# Watch.net
KiCad netlist of a schematic drawn in Altium Designer
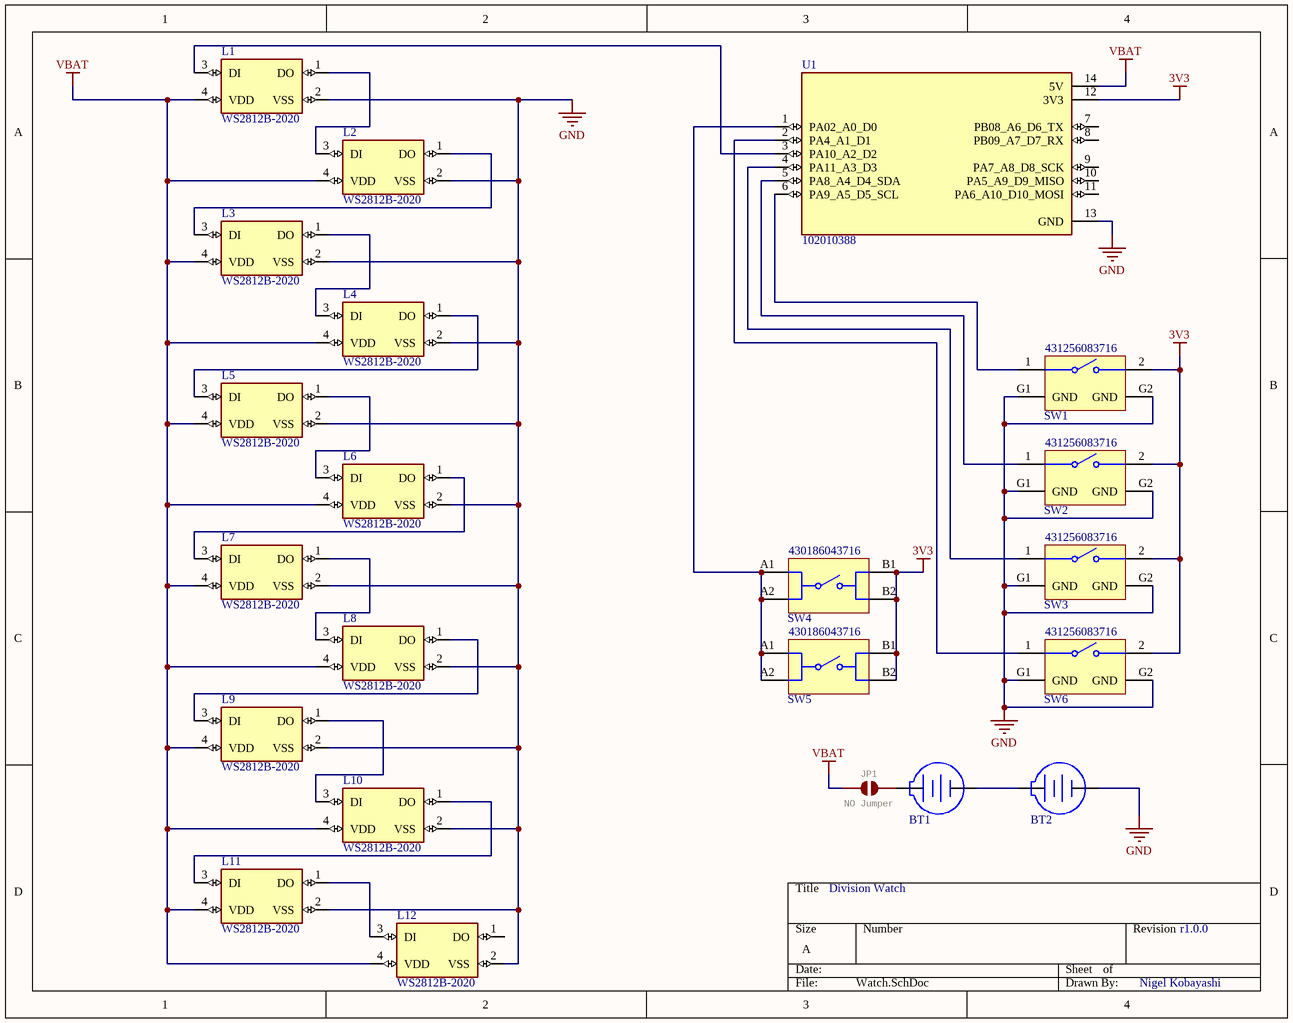
[diagram p0: Watch.SchDoc]

(export (version "E")
  (design (tool "Eeschema 10.0.6"))
  (components
    (comp (ref "BT1")
      (value "79523141")
      (footprint "79523141")
      (description "WA-BCMC Battery Holder, SMT, battery type 2016,2020,2025,2032")
      (fields (field (name "MANUFACTURER") "Wurth Elektronik"))
      (libsource (lib "WE - Electromechanical Components") (part "Battery Holder"))
    )
    (comp (ref "BT2")
      (value "79523141")
      (footprint "79523141")
      (description "WA-BCMC Battery Holder, SMT, battery type 2016,2020,2025,2032")
      (fields (field (name "MANUFACTURER") "Wurth Elektronik"))
      (libsource (lib "WE - Electromechanical Components") (part "Battery Holder"))
    )
    (comp (ref "JP1")
      (value "NO Jumper")
      (footprint "SMT-JUMPER_2_NO_SILK")
      (libsource (lib "SparkFun-Jumpers.Library") (part "JUMPER-SMT_2_NO_SILK"))
    )
    (comp (ref "L1")
      (value "WS2812B-2020")
      (footprint "WS2812B-2020")
      (description "Programmable LED; SMD; 2020; RGB; 2x2x0.84mm; 3.7Ã·5.3V; 2kHz")
      (fields (field (name "MF") "WorldSemi"))
      (libsource (lib "WS2812B-2020") (part "WS2812B-2020"))
    )
    (comp (ref "L2")
      (value "WS2812B-2020")
      (footprint "WS2812B-2020")
      (description "Programmable LED; SMD; 2020; RGB; 2x2x0.84mm; 3.7Ã·5.3V; 2kHz")
      (fields (field (name "MF") "WorldSemi"))
      (libsource (lib "WS2812B-2020") (part "WS2812B-2020"))
    )
    (comp (ref "L3")
      (value "WS2812B-2020")
      (footprint "WS2812B-2020")
      (description "Programmable LED; SMD; 2020; RGB; 2x2x0.84mm; 3.7Ã·5.3V; 2kHz")
      (fields (field (name "MF") "WorldSemi"))
      (libsource (lib "WS2812B-2020") (part "WS2812B-2020"))
    )
    (comp (ref "L4")
      (value "WS2812B-2020")
      (footprint "WS2812B-2020")
      (description "Programmable LED; SMD; 2020; RGB; 2x2x0.84mm; 3.7Ã·5.3V; 2kHz")
      (fields (field (name "MF") "WorldSemi"))
      (libsource (lib "WS2812B-2020") (part "WS2812B-2020"))
    )
    (comp (ref "L5")
      (value "WS2812B-2020")
      (footprint "WS2812B-2020")
      (description "Programmable LED; SMD; 2020; RGB; 2x2x0.84mm; 3.7Ã·5.3V; 2kHz")
      (fields (field (name "MF") "WorldSemi"))
      (libsource (lib "WS2812B-2020") (part "WS2812B-2020"))
    )
    (comp (ref "L6")
      (value "WS2812B-2020")
      (footprint "WS2812B-2020")
      (description "Programmable LED; SMD; 2020; RGB; 2x2x0.84mm; 3.7Ã·5.3V; 2kHz")
      (fields (field (name "MF") "WorldSemi"))
      (libsource (lib "WS2812B-2020") (part "WS2812B-2020"))
    )
    (comp (ref "L7")
      (value "WS2812B-2020")
      (footprint "WS2812B-2020")
      (description "Programmable LED; SMD; 2020; RGB; 2x2x0.84mm; 3.7Ã·5.3V; 2kHz")
      (fields (field (name "MF") "WorldSemi"))
      (libsource (lib "WS2812B-2020") (part "WS2812B-2020"))
    )
    (comp (ref "L8")
      (value "WS2812B-2020")
      (footprint "WS2812B-2020")
      (description "Programmable LED; SMD; 2020; RGB; 2x2x0.84mm; 3.7Ã·5.3V; 2kHz")
      (fields (field (name "MF") "WorldSemi"))
      (libsource (lib "WS2812B-2020") (part "WS2812B-2020"))
    )
    (comp (ref "L9")
      (value "WS2812B-2020")
      (footprint "WS2812B-2020")
      (description "Programmable LED; SMD; 2020; RGB; 2x2x0.84mm; 3.7Ã·5.3V; 2kHz")
      (fields (field (name "MF") "WorldSemi"))
      (libsource (lib "WS2812B-2020") (part "WS2812B-2020"))
    )
    (comp (ref "L10")
      (value "WS2812B-2020")
      (footprint "WS2812B-2020")
      (description "Programmable LED; SMD; 2020; RGB; 2x2x0.84mm; 3.7Ã·5.3V; 2kHz")
      (fields (field (name "MF") "WorldSemi"))
      (libsource (lib "WS2812B-2020") (part "WS2812B-2020"))
    )
    (comp (ref "L11")
      (value "WS2812B-2020")
      (footprint "WS2812B-2020")
      (description "Programmable LED; SMD; 2020; RGB; 2x2x0.84mm; 3.7Ã·5.3V; 2kHz")
      (fields (field (name "MF") "WorldSemi"))
      (libsource (lib "WS2812B-2020") (part "WS2812B-2020"))
    )
    (comp (ref "L12")
      (value "WS2812B-2020")
      (footprint "WS2812B-2020")
      (description "Programmable LED; SMD; 2020; RGB; 2x2x0.84mm; 3.7Ã·5.3V; 2kHz")
      (fields (field (name "MF") "WorldSemi"))
      (libsource (lib "WS2812B-2020") (part "WS2812B-2020"))
    )
    (comp (ref "SW1")
      (value "431256083716")
      (footprint "4312560837x6")
      (description "WS-TATU THT Tact Switch 6x6mm Right Angled Type with ground terminal, SPST-NO, 12VDC, 50mA, 160g")
      (fields (field (name "MANUFACTURER") "Wurth Elektronik"))
      (libsource (lib "WE - Electromechanical Components") (part "SPST-NO_2P_2GND"))
    )
    (comp (ref "SW2")
      (value "431256083716")
      (footprint "4312560837x6")
      (description "WS-TATU THT Tact Switch 6x6mm Right Angled Type with ground terminal, SPST-NO, 12VDC, 50mA, 160g")
      (fields (field (name "MANUFACTURER") "Wurth Elektronik"))
      (libsource (lib "WE - Electromechanical Components") (part "SPST-NO_2P_2GND"))
    )
    (comp (ref "SW3")
      (value "431256083716")
      (footprint "4312560837x6")
      (description "WS-TATU THT Tact Switch 6x6mm Right Angled Type with ground terminal, SPST-NO, 12VDC, 50mA, 160g")
      (fields (field (name "MANUFACTURER") "Wurth Elektronik"))
      (libsource (lib "WE - Electromechanical Components") (part "SPST-NO_2P_2GND"))
    )
    (comp (ref "SW4")
      (value "430186043716")
      (footprint "4301x60437x6")
      (description "WS-TATV THT Tact Switch 6x6mm, SPST-NO, 12VDC, 50mA, 160g")
      (fields (field (name "MANUFACTURER") "Wurth Elektronik"))
      (libsource (lib "WE - Electromechanical Components") (part "SPST-NO_4P"))
    )
    (comp (ref "SW5")
      (value "430186043716")
      (footprint "4301x60437x6")
      (description "WS-TATV THT Tact Switch 6x6mm, SPST-NO, 12VDC, 50mA, 160g")
      (fields (field (name "MANUFACTURER") "Wurth Elektronik"))
      (libsource (lib "WE - Electromechanical Components") (part "SPST-NO_4P"))
    )
    (comp (ref "SW6")
      (value "431256083716")
      (footprint "4312560837x6")
      (description "WS-TATU THT Tact Switch 6x6mm Right Angled Type with ground terminal, SPST-NO, 12VDC, 50mA, 160g")
      (fields (field (name "MANUFACTURER") "Wurth Elektronik"))
      (libsource (lib "WE - Electromechanical Components") (part "SPST-NO_2P_2GND"))
    )
    (comp (ref "U1")
      (value "102010388")
      (footprint "MODULE_102010388")
      (fields (field (name "MF") "Seeed Technology Co., Ltd"))
      (libsource (lib "102010388") (part "102010388"))
    )
  )
  (nets
    (net (code "1") (name "3V3") (class "Default")
      (node (ref "SW1") (pin "2") (pinfunction "2_2") (pintype "passive"))
      (node (ref "SW2") (pin "2") (pinfunction "2_2") (pintype "passive"))
      (node (ref "SW3") (pin "2") (pinfunction "2_2") (pintype "passive"))
      (node (ref "SW4") (pin "B1") (pinfunction "B1_B1") (pintype "passive"))
      (node (ref "SW4") (pin "B2") (pinfunction "B2_B2") (pintype "passive"))
      (node (ref "SW5") (pin "B1") (pinfunction "B1_B1") (pintype "passive"))
      (node (ref "SW5") (pin "B2") (pinfunction "B2_B2") (pintype "passive"))
      (node (ref "SW6") (pin "2") (pinfunction "2_2") (pintype "passive"))
      (node (ref "U1") (pin "12") (pinfunction "3V3_12") (pintype "power_in"))
    )
    (net (code "2") (name "GND") (class "Default")
      (node (ref "BT2") (pin "2") (pinfunction "-_2") (pintype "passive"))
      (node (ref "L1") (pin "2") (pinfunction "VSS_2") (pintype "bidirectional"))
      (node (ref "L10") (pin "2") (pinfunction "VSS_2") (pintype "bidirectional"))
      (node (ref "L11") (pin "2") (pinfunction "VSS_2") (pintype "bidirectional"))
      (node (ref "L12") (pin "2") (pinfunction "VSS_2") (pintype "bidirectional"))
      (node (ref "L2") (pin "2") (pinfunction "VSS_2") (pintype "bidirectional"))
      (node (ref "L3") (pin "2") (pinfunction "VSS_2") (pintype "bidirectional"))
      (node (ref "L4") (pin "2") (pinfunction "VSS_2") (pintype "bidirectional"))
      (node (ref "L5") (pin "2") (pinfunction "VSS_2") (pintype "bidirectional"))
      (node (ref "L6") (pin "2") (pinfunction "VSS_2") (pintype "bidirectional"))
      (node (ref "L7") (pin "2") (pinfunction "VSS_2") (pintype "bidirectional"))
      (node (ref "L8") (pin "2") (pinfunction "VSS_2") (pintype "bidirectional"))
      (node (ref "L9") (pin "2") (pinfunction "VSS_2") (pintype "bidirectional"))
      (node (ref "SW1") (pin "G1") (pinfunction "GND_G1") (pintype "passive"))
      (node (ref "SW1") (pin "G2") (pinfunction "GND_G2") (pintype "passive"))
      (node (ref "SW2") (pin "G1") (pinfunction "GND_G1") (pintype "passive"))
      (node (ref "SW2") (pin "G2") (pinfunction "GND_G2") (pintype "passive"))
      (node (ref "SW3") (pin "G1") (pinfunction "GND_G1") (pintype "passive"))
      (node (ref "SW3") (pin "G2") (pinfunction "GND_G2") (pintype "passive"))
      (node (ref "SW6") (pin "G1") (pinfunction "GND_G1") (pintype "passive"))
      (node (ref "SW6") (pin "G2") (pinfunction "GND_G2") (pintype "passive"))
      (node (ref "U1") (pin "13") (pinfunction "GND_13") (pintype "power_in"))
    )
    (net (code "3") (name "Net-(BT1-+)") (class "Default")
      (node (ref "BT1") (pin "1") (pinfunction "+_1") (pintype "passive"))
      (node (ref "JP1") (pin "2") (pinfunction "2_2") (pintype "passive"))
    )
    (net (code "4") (name "Net-(BT1--)") (class "Default")
      (node (ref "BT1") (pin "2") (pinfunction "-_2") (pintype "passive"))
      (node (ref "BT2") (pin "1") (pinfunction "+_1") (pintype "passive"))
    )
    (net (code "5") (name "Net-(L1-DI)") (class "Default")
      (node (ref "L1") (pin "3") (pinfunction "DI_3") (pintype "bidirectional"))
      (node (ref "U1") (pin "3") (pinfunction "PA10_A2_D2_3") (pintype "bidirectional"))
    )
    (net (code "6") (name "Net-(L1-DO)") (class "Default")
      (node (ref "L1") (pin "1") (pinfunction "DO_1") (pintype "bidirectional"))
      (node (ref "L2") (pin "3") (pinfunction "DI_3") (pintype "bidirectional"))
    )
    (net (code "7") (name "Net-(L2-DO)") (class "Default")
      (node (ref "L2") (pin "1") (pinfunction "DO_1") (pintype "bidirectional"))
      (node (ref "L3") (pin "3") (pinfunction "DI_3") (pintype "bidirectional"))
    )
    (net (code "8") (name "Net-(L3-DO)") (class "Default")
      (node (ref "L3") (pin "1") (pinfunction "DO_1") (pintype "bidirectional"))
      (node (ref "L4") (pin "3") (pinfunction "DI_3") (pintype "bidirectional"))
    )
    (net (code "9") (name "Net-(L4-DO)") (class "Default")
      (node (ref "L4") (pin "1") (pinfunction "DO_1") (pintype "bidirectional"))
      (node (ref "L5") (pin "3") (pinfunction "DI_3") (pintype "bidirectional"))
    )
    (net (code "10") (name "Net-(L5-DO)") (class "Default")
      (node (ref "L5") (pin "1") (pinfunction "DO_1") (pintype "bidirectional"))
      (node (ref "L6") (pin "3") (pinfunction "DI_3") (pintype "bidirectional"))
    )
    (net (code "11") (name "Net-(L6-DO)") (class "Default")
      (node (ref "L6") (pin "1") (pinfunction "DO_1") (pintype "bidirectional"))
      (node (ref "L7") (pin "3") (pinfunction "DI_3") (pintype "bidirectional"))
    )
    (net (code "12") (name "Net-(L7-DO)") (class "Default")
      (node (ref "L7") (pin "1") (pinfunction "DO_1") (pintype "bidirectional"))
      (node (ref "L8") (pin "3") (pinfunction "DI_3") (pintype "bidirectional"))
    )
    (net (code "13") (name "Net-(L8-DO)") (class "Default")
      (node (ref "L8") (pin "1") (pinfunction "DO_1") (pintype "bidirectional"))
      (node (ref "L9") (pin "3") (pinfunction "DI_3") (pintype "bidirectional"))
    )
    (net (code "14") (name "Net-(L10-DI)") (class "Default")
      (node (ref "L10") (pin "3") (pinfunction "DI_3") (pintype "bidirectional"))
      (node (ref "L9") (pin "1") (pinfunction "DO_1") (pintype "bidirectional"))
    )
    (net (code "15") (name "Net-(L10-DO)") (class "Default")
      (node (ref "L10") (pin "1") (pinfunction "DO_1") (pintype "bidirectional"))
      (node (ref "L11") (pin "3") (pinfunction "DI_3") (pintype "bidirectional"))
    )
    (net (code "16") (name "Net-(L11-DO)") (class "Default")
      (node (ref "L11") (pin "1") (pinfunction "DO_1") (pintype "bidirectional"))
      (node (ref "L12") (pin "3") (pinfunction "DI_3") (pintype "bidirectional"))
    )
    (net (code "17") (name "Net-(U1-PA02_A0_D0)") (class "Default")
      (node (ref "SW4") (pin "A1") (pinfunction "A1_A1") (pintype "passive"))
      (node (ref "SW4") (pin "A2") (pinfunction "A2_A2") (pintype "passive"))
      (node (ref "SW5") (pin "A1") (pinfunction "A1_A1") (pintype "passive"))
      (node (ref "SW5") (pin "A2") (pinfunction "A2_A2") (pintype "passive"))
      (node (ref "U1") (pin "1") (pinfunction "PA02_A0_D0_1") (pintype "bidirectional"))
    )
    (net (code "18") (name "Net-(U1-PA4_A1_D1)") (class "Default")
      (node (ref "SW6") (pin "1") (pinfunction "1_1") (pintype "passive"))
      (node (ref "U1") (pin "2") (pinfunction "PA4_A1_D1_2") (pintype "bidirectional"))
    )
    (net (code "19") (name "Net-(U1-PA8_A4_D4_SDA)") (class "Default")
      (node (ref "SW2") (pin "1") (pinfunction "1_1") (pintype "passive"))
      (node (ref "U1") (pin "5") (pinfunction "PA8_A4_D4_SDA_5") (pintype "bidirectional"))
    )
    (net (code "20") (name "Net-(U1-PA9_A5_D5_SCL)") (class "Default")
      (node (ref "SW1") (pin "1") (pinfunction "1_1") (pintype "passive"))
      (node (ref "U1") (pin "6") (pinfunction "PA9_A5_D5_SCL_6") (pintype "bidirectional"))
    )
    (net (code "21") (name "Net-(U1-PA11_A3_D3)") (class "Default")
      (node (ref "SW3") (pin "1") (pinfunction "1_1") (pintype "passive"))
      (node (ref "U1") (pin "4") (pinfunction "PA11_A3_D3_4") (pintype "bidirectional"))
    )
    (net (code "22") (name "VBAT") (class "Default")
      (node (ref "JP1") (pin "1") (pinfunction "1_1") (pintype "passive"))
      (node (ref "L1") (pin "4") (pinfunction "VDD_4") (pintype "bidirectional"))
      (node (ref "L10") (pin "4") (pinfunction "VDD_4") (pintype "bidirectional"))
      (node (ref "L11") (pin "4") (pinfunction "VDD_4") (pintype "bidirectional"))
      (node (ref "L12") (pin "4") (pinfunction "VDD_4") (pintype "bidirectional"))
      (node (ref "L2") (pin "4") (pinfunction "VDD_4") (pintype "bidirectional"))
      (node (ref "L3") (pin "4") (pinfunction "VDD_4") (pintype "bidirectional"))
      (node (ref "L4") (pin "4") (pinfunction "VDD_4") (pintype "bidirectional"))
      (node (ref "L5") (pin "4") (pinfunction "VDD_4") (pintype "bidirectional"))
      (node (ref "L6") (pin "4") (pinfunction "VDD_4") (pintype "bidirectional"))
      (node (ref "L7") (pin "4") (pinfunction "VDD_4") (pintype "bidirectional"))
      (node (ref "L8") (pin "4") (pinfunction "VDD_4") (pintype "bidirectional"))
      (node (ref "L9") (pin "4") (pinfunction "VDD_4") (pintype "bidirectional"))
      (node (ref "U1") (pin "14") (pinfunction "5V_14") (pintype "power_in"))
    )
    (net (code "23") (name "unconnected-(L12-DO-Pad1)") (class "Default")
      (node (ref "L12") (pin "1") (pinfunction "DO_1") (pintype "bidirectional"))
    )
    (net (code "24") (name "unconnected-(U1-PA5_A9_D9_MISO-Pad10)") (class "Default")
      (node (ref "U1") (pin "10") (pinfunction "PA5_A9_D9_MISO_10") (pintype "bidirectional"))
    )
    (net (code "25") (name "unconnected-(U1-PA6_A10_D10_MOSI-Pad11)") (class "Default")
      (node (ref "U1") (pin "11") (pinfunction "PA6_A10_D10_MOSI_11") (pintype "bidirectional"))
    )
    (net (code "26") (name "unconnected-(U1-PA7_A8_D8_SCK-Pad9)") (class "Default")
      (node (ref "U1") (pin "9") (pinfunction "PA7_A8_D8_SCK_9") (pintype "bidirectional"))
    )
    (net (code "27") (name "unconnected-(U1-PB08_A6_D6_TX-Pad7)") (class "Default")
      (node (ref "U1") (pin "7") (pinfunction "PB08_A6_D6_TX_7") (pintype "bidirectional"))
    )
    (net (code "28") (name "unconnected-(U1-PB09_A7_D7_RX-Pad8)") (class "Default")
      (node (ref "U1") (pin "8") (pinfunction "PB09_A7_D7_RX_8") (pintype "bidirectional"))
    )
  )
)
